# PCB_buttons.net
KiCad netlist of a schematic drawn in EAGLE
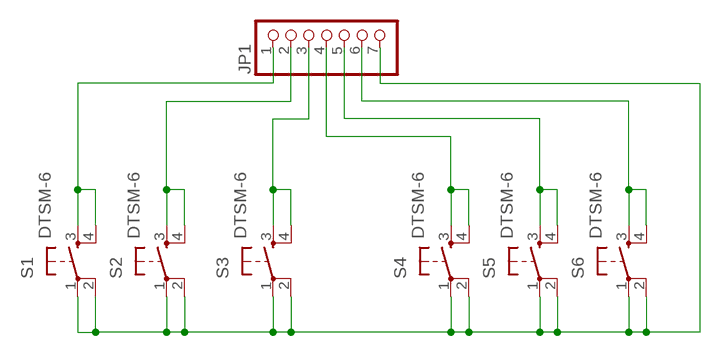
[diagram p0: schematic, sheet 1]

(export (version "E")
  (design (tool "Eeschema 10.0.6"))
  (components
    (comp (ref "JP1")
      (value "PINHD-1X7")
      (footprint "eagle-import:1X07")
      (libsource (lib "eagle-import") (part "PINHD-1X7"))
    )
    (comp (ref "S1")
      (value "DTSM-6")
      (footprint "eagle-import:DTSM-6")
      (libsource (lib "eagle-import") (part "DTSM-6"))
    )
    (comp (ref "S2")
      (value "DTSM-6")
      (footprint "eagle-import:DTSM-6")
      (libsource (lib "eagle-import") (part "DTSM-6"))
    )
    (comp (ref "S3")
      (value "DTSM-6")
      (footprint "eagle-import:DTSM-6")
      (libsource (lib "eagle-import") (part "DTSM-6"))
    )
    (comp (ref "S4")
      (value "DTSM-6")
      (footprint "eagle-import:DTSM-6")
      (libsource (lib "eagle-import") (part "DTSM-6"))
    )
    (comp (ref "S5")
      (value "DTSM-6")
      (footprint "eagle-import:DTSM-6")
      (libsource (lib "eagle-import") (part "DTSM-6"))
    )
    (comp (ref "S6")
      (value "DTSM-6")
      (footprint "eagle-import:DTSM-6")
      (libsource (lib "eagle-import") (part "DTSM-6"))
    )
  )
  (nets
    (net (code "1") (name "Net-(JP1-Pad1)") (class "Default")
      (node (ref "JP1") (pin "1") (pinfunction "1_1") (pintype "passive"))
      (node (ref "S1") (pin "3") (pinfunction "3_3") (pintype "passive"))
      (node (ref "S1") (pin "4") (pinfunction "4_4") (pintype "passive"))
    )
    (net (code "2") (name "Net-(JP1-Pad2)") (class "Default")
      (node (ref "JP1") (pin "2") (pinfunction "2_2") (pintype "passive"))
      (node (ref "S2") (pin "3") (pinfunction "3_3") (pintype "passive"))
      (node (ref "S2") (pin "4") (pinfunction "4_4") (pintype "passive"))
    )
    (net (code "3") (name "Net-(JP1-Pad3)") (class "Default")
      (node (ref "JP1") (pin "3") (pinfunction "3_3") (pintype "passive"))
      (node (ref "S3") (pin "3") (pinfunction "3_3") (pintype "passive"))
      (node (ref "S3") (pin "4") (pinfunction "4_4") (pintype "passive"))
    )
    (net (code "4") (name "Net-(JP1-Pad4)") (class "Default")
      (node (ref "JP1") (pin "4") (pinfunction "4_4") (pintype "passive"))
      (node (ref "S4") (pin "3") (pinfunction "3_3") (pintype "passive"))
      (node (ref "S4") (pin "4") (pinfunction "4_4") (pintype "passive"))
    )
    (net (code "5") (name "Net-(JP1-Pad5)") (class "Default")
      (node (ref "JP1") (pin "5") (pinfunction "5_5") (pintype "passive"))
      (node (ref "S5") (pin "3") (pinfunction "3_3") (pintype "passive"))
      (node (ref "S5") (pin "4") (pinfunction "4_4") (pintype "passive"))
    )
    (net (code "6") (name "Net-(JP1-Pad6)") (class "Default")
      (node (ref "JP1") (pin "6") (pinfunction "6_6") (pintype "passive"))
      (node (ref "S6") (pin "3") (pinfunction "3_3") (pintype "passive"))
      (node (ref "S6") (pin "4") (pinfunction "4_4") (pintype "passive"))
    )
    (net (code "7") (name "Net-(JP1-Pad7)") (class "Default")
      (node (ref "JP1") (pin "7") (pinfunction "7_7") (pintype "passive"))
      (node (ref "S1") (pin "1") (pinfunction "1_1") (pintype "passive"))
      (node (ref "S1") (pin "2") (pinfunction "2_2") (pintype "passive"))
      (node (ref "S2") (pin "1") (pinfunction "1_1") (pintype "passive"))
      (node (ref "S2") (pin "2") (pinfunction "2_2") (pintype "passive"))
      (node (ref "S3") (pin "1") (pinfunction "1_1") (pintype "passive"))
      (node (ref "S3") (pin "2") (pinfunction "2_2") (pintype "passive"))
      (node (ref "S4") (pin "1") (pinfunction "1_1") (pintype "passive"))
      (node (ref "S4") (pin "2") (pinfunction "2_2") (pintype "passive"))
      (node (ref "S5") (pin "1") (pinfunction "1_1") (pintype "passive"))
      (node (ref "S5") (pin "2") (pinfunction "2_2") (pintype "passive"))
      (node (ref "S6") (pin "1") (pinfunction "1_1") (pintype "passive"))
      (node (ref "S6") (pin "2") (pinfunction "2_2") (pintype "passive"))
    )
  )
)
